# schem.net
KiCad netlist of a schematic drawn in EAGLE
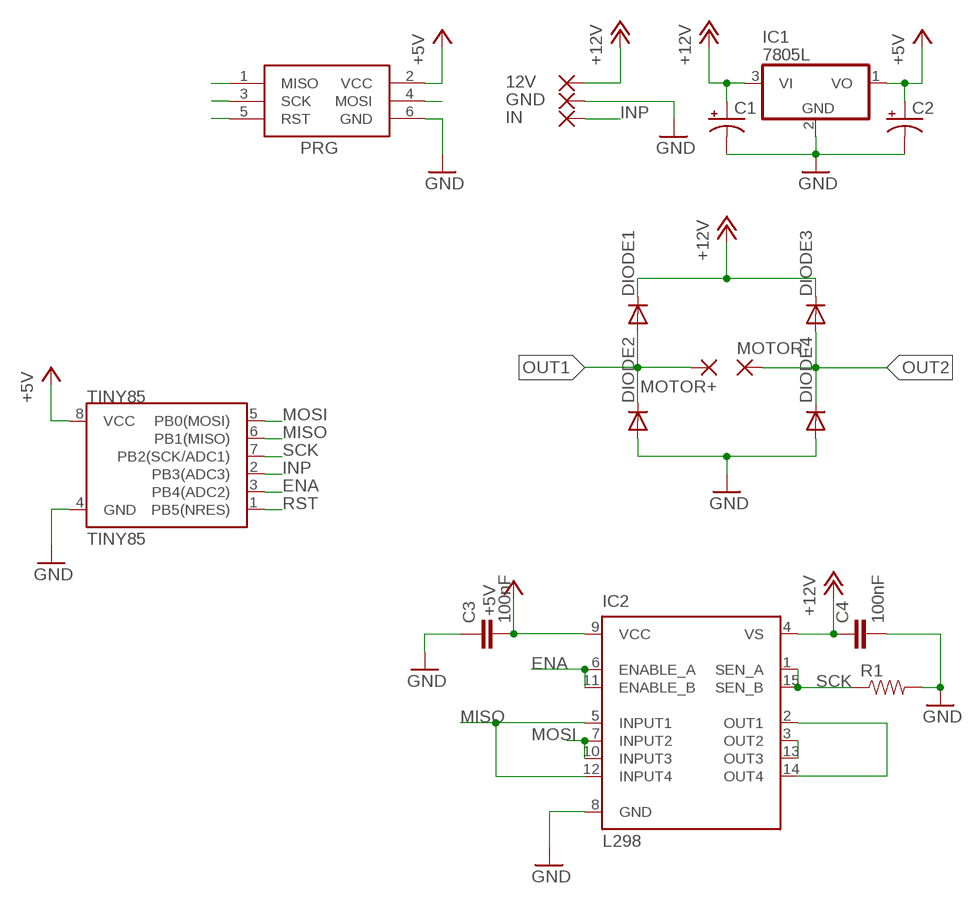
[diagram p0: schematic, sheet 1]

(export (version "E")
  (design (tool "Eeschema 10.0.6"))
  (components
    (comp (ref "12V")
      (value "3,81/1,4")
      (footprint "eagle-import:3,81_1,4")
      (libsource (lib "eagle-import") (part "3,81/1,4"))
    )
    (comp (ref "C1")
      (value "CPOL-USE2.5-6")
      (footprint "eagle-import:E2,5-6")
      (libsource (lib "eagle-import") (part "CPOL-USE2.5-6"))
    )
    (comp (ref "C2")
      (value "CPOL-USE2.5-6")
      (footprint "eagle-import:E2,5-6")
      (libsource (lib "eagle-import") (part "CPOL-USE2.5-6"))
    )
    (comp (ref "C3")
      (value "100nF")
      (footprint "eagle-import:CAP-PTH-SMALL2")
      (libsource (lib "eagle-import") (part "CAPPTH2"))
    )
    (comp (ref "C4")
      (value "100nF")
      (footprint "eagle-import:CAP-PTH-SMALL2")
      (libsource (lib "eagle-import") (part "CAPPTH2"))
    )
    (comp (ref "DIODE1")
      (value "DIODE-DO41-7.6")
      (footprint "eagle-import:DO41-7.6")
      (libsource (lib "eagle-import") (part "DIODE-DO41-7.6"))
    )
    (comp (ref "DIODE2")
      (value "DIODE-DO41-7.6")
      (footprint "eagle-import:DO41-7.6")
      (libsource (lib "eagle-import") (part "DIODE-DO41-7.6"))
    )
    (comp (ref "DIODE3")
      (value "DIODE-DO41-7.6")
      (footprint "eagle-import:DO41-7.6")
      (libsource (lib "eagle-import") (part "DIODE-DO41-7.6"))
    )
    (comp (ref "DIODE4")
      (value "DIODE-DO41-7.6")
      (footprint "eagle-import:DO41-7.6")
      (libsource (lib "eagle-import") (part "DIODE-DO41-7.6"))
    )
    (comp (ref "GND")
      (value "3,81/1,4")
      (footprint "eagle-import:3,81_1,4")
      (libsource (lib "eagle-import") (part "3,81/1,4"))
    )
    (comp (ref "IC1")
      (value "7805L")
      (footprint "eagle-import:TO92")
      (libsource (lib "eagle-import") (part "78L05"))
    )
    (comp (ref "IC2")
      (value "L298")
      (footprint "eagle-import:MULTIWATT-15")
      (fields (field (name "MPN") "L298N"))
      (libsource (lib "eagle-import") (part "L298"))
    )
    (comp (ref "IN")
      (value "1,6/0,9")
      (footprint "eagle-import:1,6_0,9")
      (libsource (lib "eagle-import") (part "1,6/0,9"))
    )
    (comp (ref "MOTOR+")
      (value "3,81/1,4")
      (footprint "eagle-import:3,81_1,4")
      (libsource (lib "eagle-import") (part "3,81/1,4"))
    )
    (comp (ref "MOTOR-")
      (value "3,81/1,4")
      (footprint "eagle-import:3,81_1,4")
      (libsource (lib "eagle-import") (part "3,81/1,4"))
    )
    (comp (ref "PRG")
      (value "AVRISP-6")
      (footprint "eagle-import:AVRISP")
      (libsource (lib "eagle-import") (part "AVRISP-6"))
    )
    (comp (ref "R1")
      (value "RESISTORPTH-1/4W")
      (footprint "eagle-import:AXIAL-0.4")
      (libsource (lib "eagle-import") (part "RESISTORPTH-1/4W"))
    )
    (comp (ref "TINY85")
      (value "TINY85")
      (footprint "eagle-import:DIP08")
      (libsource (lib "eagle-import") (part "ATTINY45TINY85-20-DIP"))
    )
  )
  (nets
    (net (code "1") (name "+5V") (class "Default")
      (node (ref "C2") (pin "+") (pinfunction "+_+") (pintype "passive"))
      (node (ref "C3") (pin "2") (pinfunction "2_2") (pintype "passive"))
      (node (ref "IC1") (pin "1") (pinfunction "VO_1") (pintype "passive"))
      (node (ref "IC2") (pin "9") (pinfunction "VCC_9") (pintype "power_in"))
      (node (ref "PRG") (pin "2") (pinfunction "VCC_2") (pintype "power_in"))
      (node (ref "TINY85") (pin "8") (pinfunction "VCC_8") (pintype "bidirectional"))
    )
    (net (code "2") (name "+12V") (class "Default")
      (node (ref "12V") (pin "1") (pinfunction "P_1") (pintype "passive"))
      (node (ref "C1") (pin "+") (pinfunction "+_+") (pintype "passive"))
      (node (ref "C4") (pin "1") (pinfunction "1_1") (pintype "passive"))
      (node (ref "DIODE1") (pin "C") (pinfunction "C_C") (pintype "passive"))
      (node (ref "DIODE3") (pin "C") (pinfunction "C_C") (pintype "passive"))
      (node (ref "IC1") (pin "3") (pinfunction "VI_3") (pintype "input"))
      (node (ref "IC2") (pin "4") (pinfunction "VS_4") (pintype "power_in"))
    )
    (net (code "3") (name "/ENA") (class "Default")
      (node (ref "IC2") (pin "11") (pinfunction "ENABLE_B_11") (pintype "input"))
      (node (ref "IC2") (pin "6") (pinfunction "ENABLE_A_6") (pintype "input"))
      (node (ref "TINY85") (pin "3") (pinfunction "PB4(ADC2)_3") (pintype "bidirectional"))
    )
    (net (code "4") (name "/INP") (class "Default")
      (node (ref "IN") (pin "1") (pinfunction "P_1") (pintype "passive"))
      (node (ref "TINY85") (pin "2") (pinfunction "PB3(ADC3)_2") (pintype "bidirectional"))
    )
    (net (code "5") (name "/MISO") (class "Default")
      (node (ref "IC2") (pin "12") (pinfunction "INPUT4_12") (pintype "input"))
      (node (ref "IC2") (pin "5") (pinfunction "INPUT1_5") (pintype "input"))
      (node (ref "PRG") (pin "1") (pinfunction "MISO_1") (pintype "input"))
      (node (ref "TINY85") (pin "6") (pinfunction "PB1(MISO)_6") (pintype "bidirectional"))
    )
    (net (code "6") (name "/MOSI") (class "Default")
      (node (ref "IC2") (pin "10") (pinfunction "INPUT3_10") (pintype "input"))
      (node (ref "IC2") (pin "7") (pinfunction "INPUT2_7") (pintype "input"))
      (node (ref "PRG") (pin "4") (pinfunction "MOSI_4") (pintype "output"))
      (node (ref "TINY85") (pin "5") (pinfunction "PB0(MOSI)_5") (pintype "bidirectional"))
    )
    (net (code "7") (name "/RST") (class "Default")
      (node (ref "PRG") (pin "5") (pinfunction "RST_5") (pintype "output"))
      (node (ref "TINY85") (pin "1") (pinfunction "PB5(NRES)_1") (pintype "bidirectional"))
    )
    (net (code "8") (name "/SCK") (class "Default")
      (node (ref "IC2") (pin "1") (pinfunction "SEN_A_1") (pintype "input"))
      (node (ref "IC2") (pin "15") (pinfunction "SEN_B_15") (pintype "input"))
      (node (ref "PRG") (pin "3") (pinfunction "SCK_3") (pintype "output"))
      (node (ref "R1") (pin "P$1") (pinfunction "1_P$1") (pintype "passive"))
      (node (ref "TINY85") (pin "7") (pinfunction "PB2(SCK/ADC1)_7") (pintype "bidirectional"))
    )
    (net (code "9") (name "GND") (class "Default")
      (node (ref "C1") (pin "-") (pinfunction "-_-") (pintype "passive"))
      (node (ref "C2") (pin "-") (pinfunction "-_-") (pintype "passive"))
      (node (ref "C3") (pin "1") (pinfunction "1_1") (pintype "passive"))
      (node (ref "C4") (pin "2") (pinfunction "2_2") (pintype "passive"))
      (node (ref "DIODE2") (pin "A") (pinfunction "A_A") (pintype "passive"))
      (node (ref "DIODE4") (pin "A") (pinfunction "A_A") (pintype "passive"))
      (node (ref "GND") (pin "1") (pinfunction "P_1") (pintype "passive"))
      (node (ref "IC1") (pin "2") (pinfunction "GND_2") (pintype "passive"))
      (node (ref "IC2") (pin "8") (pinfunction "GND_8") (pintype "power_in"))
      (node (ref "PRG") (pin "6") (pinfunction "GND_6") (pintype "power_in"))
      (node (ref "R1") (pin "P$2") (pinfunction "2_P$2") (pintype "passive"))
      (node (ref "TINY85") (pin "4") (pinfunction "GND_4") (pintype "bidirectional"))
    )
    (net (code "10") (name "OUT1") (class "Default")
      (node (ref "DIODE1") (pin "A") (pinfunction "A_A") (pintype "passive"))
      (node (ref "DIODE2") (pin "C") (pinfunction "C_C") (pintype "passive"))
      (node (ref "IC2") (pin "14") (pinfunction "OUT4_14") (pintype "output"))
      (node (ref "IC2") (pin "2") (pinfunction "OUT1_2") (pintype "output"))
      (node (ref "MOTOR+") (pin "1") (pinfunction "P_1") (pintype "passive"))
    )
    (net (code "11") (name "OUT2") (class "Default")
      (node (ref "DIODE3") (pin "A") (pinfunction "A_A") (pintype "passive"))
      (node (ref "DIODE4") (pin "C") (pinfunction "C_C") (pintype "passive"))
      (node (ref "IC2") (pin "13") (pinfunction "OUT3_13") (pintype "output"))
      (node (ref "IC2") (pin "3") (pinfunction "OUT2_3") (pintype "output"))
      (node (ref "MOTOR-") (pin "1") (pinfunction "P_1") (pintype "passive"))
    )
  )
)
